# design.net
KiCad netlist of a schematic drawn in Altium Designer
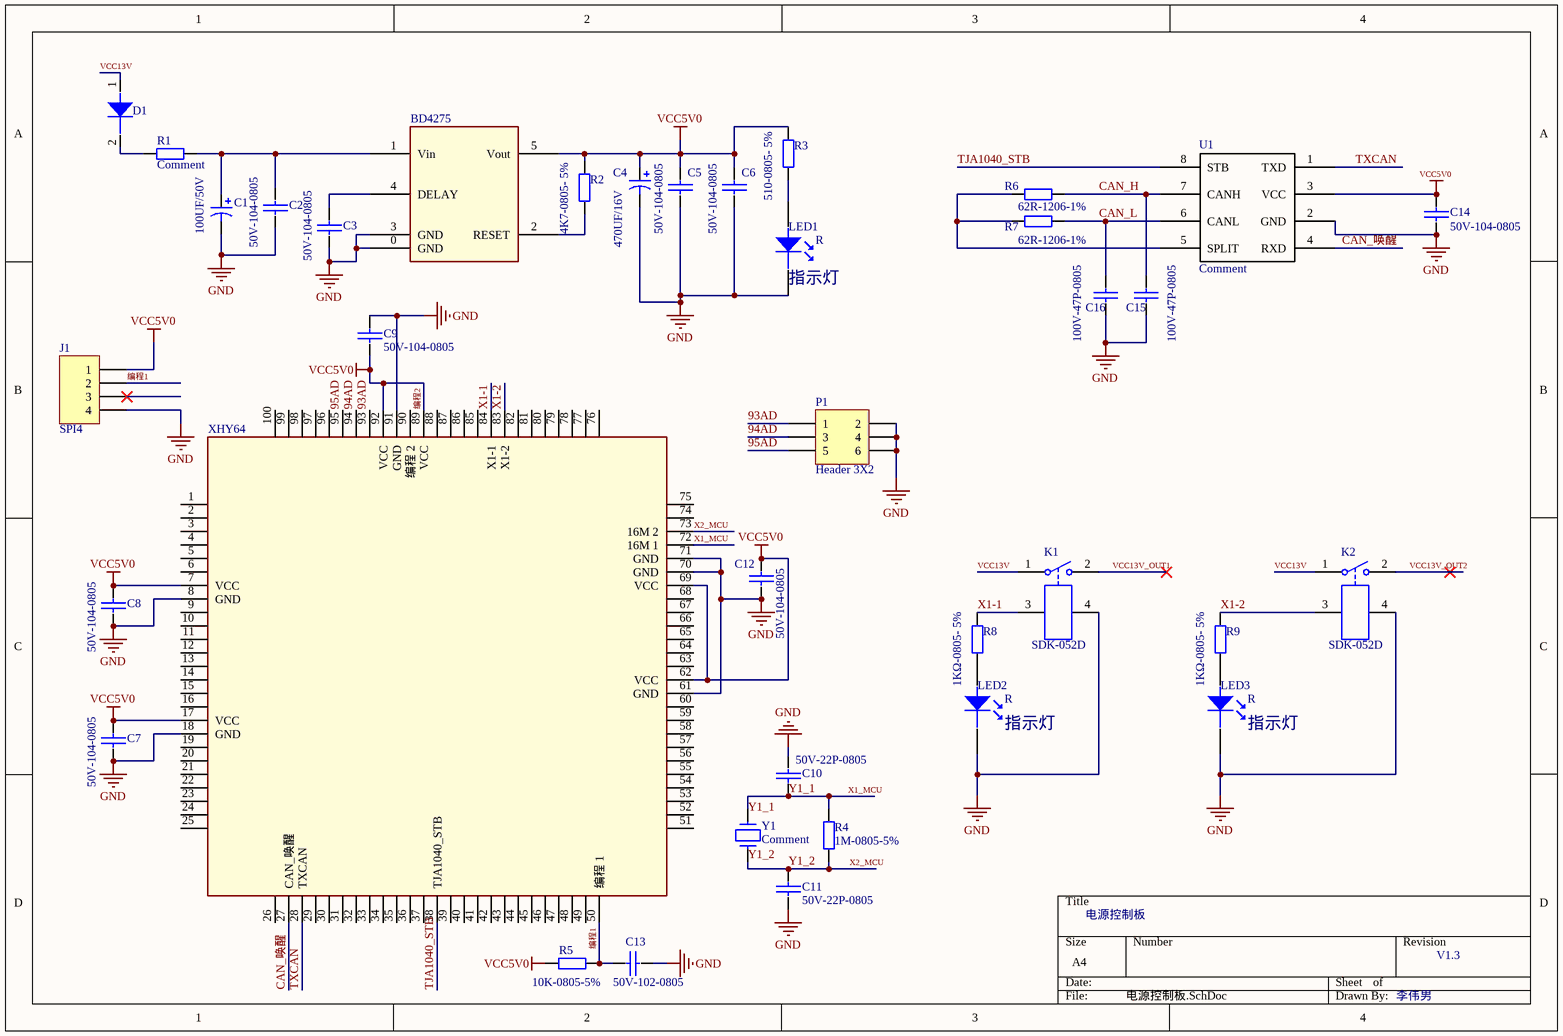
[diagram p0: 电源控制板.SchDoc]

(export (version "E")
  (design (tool "Eeschema 10.0.6"))
  (components
    (comp (ref "BD4275") (value "BD4275") (footprint "TO-263") (libsource (lib "Schlib1") (part "BD4275")))
    (comp (ref "C1")
      (value "100UF/50V")
      (footprint "RB.1/.25")
      (description "100UF      50V")
      (libsource (lib "平台图库_20170418_V1.0") (part "C470UF035S"))
    )
    (comp (ref "C2")
      (value "50V-104-0805")
      (footprint "C0805")
      (description "104     50V        10%   C0805")
      (fields (field (name "Comment") "104"))
      (libsource (lib "平台图库_20170418_V1.0") (part "C104_0805"))
    )
    (comp (ref "C3")
      (value "50V-104-0805")
      (footprint "C0805")
      (description "104     50V        10%   C0805")
      (fields (field (name "Comment") "104"))
      (libsource (lib "平台图库_20170418_V1.0") (part "C104_0805"))
    )
    (comp (ref "C4")
      (value "470UF/16V")
      (footprint "RB.1/.25")
      (description "100UF      50V      CD10X10D5")
      (libsource (lib "平台图库_20170418_V1.0") (part "C470UF016S"))
    )
    (comp (ref "C5")
      (value "50V-104-0805")
      (footprint "C0805")
      (description "104     50V        10%   C0805")
      (fields (field (name "Comment") "104"))
      (libsource (lib "平台图库_20170418_V1.0") (part "C104_0805"))
    )
    (comp (ref "C6")
      (value "50V-104-0805")
      (footprint "C0805")
      (description "104     50V        10%   C0805")
      (fields (field (name "Comment") "104"))
      (libsource (lib "平台图库_20170418_V1.0") (part "C104_0805"))
    )
    (comp (ref "C7")
      (value "50V-104-0805")
      (footprint "C0805")
      (description "104     50V        10%   C0805")
      (fields (field (name "Comment") "104"))
      (libsource (lib "平台图库_20170418_V1.0") (part "C104_0805"))
    )
    (comp (ref "C8")
      (value "50V-104-0805")
      (footprint "C0805")
      (description "104     50V        10%   C0805")
      (fields (field (name "Comment") "104"))
      (libsource (lib "平台图库_20170418_V1.0") (part "C104_0805"))
    )
    (comp (ref "C9")
      (value "50V-104-0805")
      (footprint "C0805")
      (description "104     50V        10%   C0805")
      (fields (field (name "Comment") "104"))
      (libsource (lib "平台图库_20170418_V1.0") (part "C104_0805"))
    )
    (comp (ref "C10")
      (value "50V-22P-0805")
      (footprint "C0805")
      (description "22P     50V        10%   C0805")
      (fields (field (name "Comment") "22P"))
      (libsource (lib "平台图库_20170418_V1.0") (part "C22P_0805"))
    )
    (comp (ref "C11")
      (value "50V-22P-0805")
      (footprint "C0805")
      (description "22P     50V        10%   C0805")
      (fields (field (name "Comment") "22P"))
      (libsource (lib "平台图库_20170418_V1.0") (part "C22P_0805"))
    )
    (comp (ref "C12")
      (value "50V-104-0805")
      (footprint "C0805")
      (description "104     50V        10%   C0805")
      (fields (field (name "Comment") "104"))
      (libsource (lib "平台图库_20170418_V1.0") (part "C104_0805"))
    )
    (comp (ref "C13")
      (value "50V-102-0805")
      (footprint "C0805")
      (description "104     50V        10%   C0805")
      (fields (field (name "Comment") "104"))
      (libsource (lib "平台图库_20170418_V1.0") (part "C102_0805"))
    )
    (comp (ref "C14")
      (value "50V-104-0805")
      (footprint "C0805")
      (description "104     50V        10%   C0805")
      (fields (field (name "Comment") "104"))
      (libsource (lib "平台图库_20170418_V1.0") (part "C104_0805"))
    )
    (comp (ref "C15")
      (value "100V-47P-0805")
      (footprint "C0805")
      (description "47P    100V        10%   C0805")
      (fields (field (name "Comment") "47P-100V"))
      (libsource (lib "平台图库_20170418_V1.0") (part "C47P_100V_0805"))
    )
    (comp (ref "C16")
      (value "100V-47P-0805")
      (footprint "C0805")
      (description "47P    100V        10%   C0805")
      (fields (field (name "Comment") "47P-100V"))
      (libsource (lib "平台图库_20170418_V1.0") (part "C47P_100V_0805"))
    )
    (comp (ref "D1") (value "M7") (footprint "M7-A") (libsource (lib "平台图库_20170418_V1.0") (part "TVS")))
    (comp (ref "J1")
      (value "SPI4")
      (footprint "HDR1X4")
      (description "单排针，Header, 4-Pin")
      (fields (field (name "PUBLISHER") "Altium Limited"))
      (libsource (lib "TYW_Discrete") (part "Header 4"))
    )
    (comp (ref "K1")
      (value "SDK-052D")
      (footprint "SDK-052D")
      (fields (field (name "PUBLISHER") "Altium Limited"))
      (libsource (lib "Miscellaneous Devices") (part "Relay-SPST"))
    )
    (comp (ref "K2")
      (value "SDK-052D")
      (footprint "SDK-052D")
      (fields (field (name "PUBLISHER") "Altium Limited"))
      (libsource (lib "Miscellaneous Devices") (part "Relay-SPST"))
    )
    (comp (ref "LED1")
      (value "R")
      (footprint "1206-2")
      (description "LED_R")
      (libsource (lib "平台图库_20170418_V1.0") (part "LED_R"))
    )
    (comp (ref "LED2")
      (value "R")
      (footprint "1206-2")
      (description "LED_R")
      (libsource (lib "平台图库_20170418_V1.0") (part "LED_R"))
    )
    (comp (ref "LED3")
      (value "R")
      (footprint "1206-2")
      (description "LED_R")
      (libsource (lib "平台图库_20170418_V1.0") (part "LED_R"))
    )
    (comp (ref "P1")
      (value "Header 3X2")
      (footprint "HDR2X3")
      (description "Header, 3-Pin, Dual row")
      (fields (field (name "PUBLISHER") "Altium Limited"))
      (libsource (lib "Miscellaneous Connectors") (part "Header 3X2"))
    )
    (comp (ref "R1")
      (value "Comment")
      (footprint "2WR")
      (description "8R2                                2W")
      (libsource (lib "平台图库_20170418_V1.0") (part "R8R22W"))
    )
    (comp (ref "R2")
      (value "4K7-0805- 5%")
      (footprint "0805")
      (description "4K7     1/8W    5%   R0805")
      (fields (field (name "Comment") "4K7"))
      (libsource (lib "平台图库_20170418_V1.0") (part "R4K7_0805_5%"))
    )
    (comp (ref "R3")
      (value "510-0805- 5%")
      (footprint "0805_2")
      (description "510Ω    5%   R0805")
      (fields (field (name "Comment") "510Ω"))
      (libsource (lib "Miscellaneous Connectors") (part "R4K7_0805_5%"))
    )
    (comp (ref "R4")
      (value "1M-0805-5%")
      (footprint "0805")
      (description "1M    1/8W    5%   R0805")
      (fields (field (name "Comment") "1M"))
      (libsource (lib "平台图库_20170418_V1.0") (part "R1M_0805_5%"))
    )
    (comp (ref "R5")
      (value "10K-0805-5%")
      (footprint "0805")
      (description "10K     1/8W    5%   R0805")
      (fields (field (name "Comment") "10K"))
      (libsource (lib "平台图库_20170418_V1.0") (part "R10K_0805_5%"))
    )
    (comp (ref "R6")
      (value "62R-1206-1%")
      (footprint "1206")
      (description "62R    1/4W     1%   R1206")
      (fields (field (name "Comment") "62R-J"))
      (libsource (lib "平台图库_20170418_V1.0") (part "R62R_1206_1%"))
    )
    (comp (ref "R7")
      (value "62R-1206-1%")
      (footprint "1206")
      (description "62R    1/4W     1%   R1206")
      (fields (field (name "Comment") "62R-J"))
      (libsource (lib "平台图库_20170418_V1.0") (part "R62R_1206_1%"))
    )
    (comp (ref "R8")
      (value "1KΩ-0805- 5%")
      (footprint "0805_2")
      (description "1KΩ    5%   R0805")
      (fields (field (name "Comment") "1KΩ"))
      (libsource (lib "Miscellaneous Connectors") (part "R4K7_0805_5%"))
    )
    (comp (ref "R9")
      (value "1KΩ-0805- 5%")
      (footprint "0805_2")
      (description "1KΩ    5%   R0805")
      (fields (field (name "Comment") "1KΩ"))
      (libsource (lib "Miscellaneous Connectors") (part "R4K7_0805_5%"))
    )
    (comp (ref "U1")
      (value "Comment")
      (footprint "SO-8")
      (description "CAN驱动芯片")
      (libsource (lib "平台图库_20170418_V1.0") (part "TJA1042"))
    )
    (comp (ref "XHY64") (value "XHY64") (footprint "QUAD100") (libsource (lib "Schlib1") (part "XHY64")))
    (comp (ref "Y1")
      (value "Comment")
      (footprint "16M")
      (description "晶体，4M")
      (libsource (lib "TYW_Discrete") (part "XTAL"))
    )
  )
  (nets
    (net (code "1") (name "/93AD") (class "Default")
      (node (ref "P1") (pin "1") (pinfunction "1_1") (pintype "passive"))
      (node (ref "XHY64") (pin "93") (pintype "passive"))
    )
    (net (code "2") (name "/94AD") (class "Default")
      (node (ref "P1") (pin "3") (pinfunction "3_3") (pintype "passive"))
      (node (ref "XHY64") (pin "94") (pintype "passive"))
    )
    (net (code "3") (name "/95AD") (class "Default")
      (node (ref "P1") (pin "5") (pinfunction "5_5") (pintype "passive"))
      (node (ref "XHY64") (pin "95") (pintype "passive"))
    )
    (net (code "4") (name "/CAN_H") (class "Default")
      (node (ref "C15") (pin "2") (pinfunction "2_2") (pintype "passive"))
      (node (ref "R6") (pin "2") (pinfunction "2_2") (pintype "passive"))
      (node (ref "U1") (pin "7") (pinfunction "CANH_7") (pintype "passive"))
    )
    (net (code "5") (name "/CAN_L") (class "Default")
      (node (ref "C16") (pin "2") (pinfunction "2_2") (pintype "passive"))
      (node (ref "R7") (pin "2") (pinfunction "2_2") (pintype "passive"))
      (node (ref "U1") (pin "6") (pinfunction "CANL_6") (pintype "passive"))
    )
    (net (code "6") (name "/CAN_唤醒") (class "Default")
      (node (ref "U1") (pin "4") (pinfunction "RXD_4") (pintype "passive"))
      (node (ref "XHY64") (pin "27") (pinfunction "CAN_唤醒_27") (pintype "passive"))
    )
    (net (code "7") (name "/TJA1040_STB") (class "Default")
      (node (ref "U1") (pin "8") (pinfunction "STB_8") (pintype "passive"))
      (node (ref "XHY64") (pin "38") (pinfunction "TJA1040_STB_38") (pintype "passive"))
    )
    (net (code "8") (name "/TXCAN") (class "Default")
      (node (ref "U1") (pin "1") (pinfunction "TXD_1") (pintype "passive"))
      (node (ref "XHY64") (pin "28") (pinfunction "TXCAN_28") (pintype "passive"))
    )
    (net (code "9") (name "/VCC13V") (class "Default")
      (node (ref "D1") (pin "1") (pinfunction "1_1") (pintype "passive"))
      (node (ref "K1") (pin "1") (pinfunction "1_1") (pintype "passive"))
      (node (ref "K2") (pin "1") (pinfunction "1_1") (pintype "passive"))
    )
    (net (code "10") (name "/VCC13V_OUT1") (class "Default")
      (node (ref "K1") (pin "2") (pinfunction "2_2") (pintype "passive+no_connect"))
    )
    (net (code "11") (name "/VCC13V_OUT2") (class "Default")
      (node (ref "K2") (pin "2") (pinfunction "2_2") (pintype "passive"))
    )
    (net (code "12") (name "/X1-1") (class "Default")
      (node (ref "K1") (pin "3") (pinfunction "3_3") (pintype "passive"))
      (node (ref "R8") (pin "2") (pinfunction "2_2") (pintype "passive"))
      (node (ref "XHY64") (pin "84") (pinfunction "X1-1_84") (pintype "passive"))
    )
    (net (code "13") (name "/X1-2") (class "Default")
      (node (ref "K2") (pin "3") (pinfunction "3_3") (pintype "passive"))
      (node (ref "R9") (pin "2") (pinfunction "2_2") (pintype "passive"))
      (node (ref "XHY64") (pin "83") (pinfunction "X1-2_83") (pintype "passive"))
    )
    (net (code "14") (name "/X1_MCU") (class "Default")
      (node (ref "C10") (pin "2") (pinfunction "2_2") (pintype "passive"))
      (node (ref "R4") (pin "2") (pinfunction "2_2") (pintype "passive"))
      (node (ref "XHY64") (pin "72") (pinfunction "16M_1_72") (pintype "passive"))
      (node (ref "Y1") (pin "2") (pinfunction "2_2") (pintype "passive"))
    )
    (net (code "15") (name "/X2_MCU") (class "Default")
      (node (ref "C11") (pin "1") (pinfunction "1_1") (pintype "passive"))
      (node (ref "R4") (pin "1") (pinfunction "1_1") (pintype "passive"))
      (node (ref "XHY64") (pin "73") (pinfunction "16M_2_73") (pintype "passive"))
      (node (ref "Y1") (pin "1") (pinfunction "1_1") (pintype "passive"))
    )
    (net (code "16") (name "/编程1") (class "Default")
      (node (ref "C13") (pin "2") (pinfunction "2_2") (pintype "passive"))
      (node (ref "J1") (pin "2") (pinfunction "2_2") (pintype "passive"))
      (node (ref "R5") (pin "1") (pinfunction "1_1") (pintype "passive"))
      (node (ref "XHY64") (pin "50") (pinfunction "编程_1_50") (pintype "passive"))
    )
    (net (code "17") (name "GND") (class "Default")
      (node (ref "BD4275") (pin "0") (pinfunction "GND_0") (pintype "passive"))
      (node (ref "BD4275") (pin "3") (pinfunction "GND_3") (pintype "passive"))
      (node (ref "C1") (pin "2") (pinfunction "2_2") (pintype "passive"))
      (node (ref "C10") (pin "1") (pinfunction "1_1") (pintype "passive"))
      (node (ref "C11") (pin "2") (pinfunction "2_2") (pintype "passive"))
      (node (ref "C12") (pin "2") (pinfunction "2_2") (pintype "passive"))
      (node (ref "C13") (pin "1") (pinfunction "1_1") (pintype "passive"))
      (node (ref "C14") (pin "1") (pinfunction "1_1") (pintype "passive"))
      (node (ref "C15") (pin "1") (pinfunction "1_1") (pintype "passive"))
      (node (ref "C16") (pin "1") (pinfunction "1_1") (pintype "passive"))
      (node (ref "C2") (pin "1") (pinfunction "1_1") (pintype "passive"))
      (node (ref "C3") (pin "1") (pinfunction "1_1") (pintype "passive"))
      (node (ref "C4") (pin "2") (pinfunction "2_2") (pintype "passive"))
      (node (ref "C5") (pin "1") (pinfunction "1_1") (pintype "passive"))
      (node (ref "C6") (pin "1") (pinfunction "1_1") (pintype "passive"))
      (node (ref "C7") (pin "2") (pinfunction "2_2") (pintype "passive"))
      (node (ref "C8") (pin "2") (pinfunction "2_2") (pintype "passive"))
      (node (ref "C9") (pin "1") (pinfunction "1_1") (pintype "passive"))
      (node (ref "J1") (pin "4") (pinfunction "4_4") (pintype "passive"))
      (node (ref "K1") (pin "4") (pinfunction "4_4") (pintype "passive"))
      (node (ref "K2") (pin "4") (pinfunction "4_4") (pintype "passive"))
      (node (ref "LED1") (pin "2") (pinfunction "2_2") (pintype "passive"))
      (node (ref "LED2") (pin "2") (pinfunction "2_2") (pintype "passive"))
      (node (ref "LED3") (pin "2") (pinfunction "2_2") (pintype "passive"))
      (node (ref "P1") (pin "2") (pinfunction "2_2") (pintype "passive"))
      (node (ref "P1") (pin "4") (pinfunction "4_4") (pintype "passive"))
      (node (ref "P1") (pin "6") (pinfunction "6_6") (pintype "passive"))
      (node (ref "U1") (pin "2") (pinfunction "GND_2") (pintype "passive"))
      (node (ref "XHY64") (pin "18") (pinfunction "GND_18") (pintype "passive"))
      (node (ref "XHY64") (pin "61") (pinfunction "GND_61") (pintype "passive"))
      (node (ref "XHY64") (pin "70") (pinfunction "GND_70") (pintype "passive"))
      (node (ref "XHY64") (pin "71") (pinfunction "GND_71") (pintype "passive"))
      (node (ref "XHY64") (pin "8") (pinfunction "GND_8") (pintype "passive"))
      (node (ref "XHY64") (pin "91") (pinfunction "GND_91") (pintype "passive"))
    )
    (net (code "18") (name "Net-(BD4275-DELAY)") (class "Default")
      (node (ref "BD4275") (pin "4") (pinfunction "DELAY_4") (pintype "passive"))
      (node (ref "C3") (pin "2") (pinfunction "2_2") (pintype "passive"))
    )
    (net (code "19") (name "Net-(BD4275-RESET)") (class "Default")
      (node (ref "BD4275") (pin "2") (pinfunction "RESET_2") (pintype "passive"))
      (node (ref "R2") (pin "1") (pinfunction "1_1") (pintype "passive"))
    )
    (net (code "20") (name "Net-(BD4275-Vin)") (class "Default")
      (node (ref "BD4275") (pin "1") (pinfunction "Vin_1") (pintype "passive"))
      (node (ref "C1") (pin "1") (pinfunction "1_1") (pintype "passive"))
      (node (ref "C2") (pin "2") (pinfunction "2_2") (pintype "passive"))
      (node (ref "R1") (pin "1") (pinfunction "1_1") (pintype "passive"))
    )
    (net (code "21") (name "Net-(D1-Pad2)") (class "Default")
      (node (ref "D1") (pin "2") (pinfunction "2_2") (pintype "passive"))
      (node (ref "R1") (pin "2") (pinfunction "2_2") (pintype "passive"))
    )
    (net (code "22") (name "Net-(LED1-Pad1)") (class "Default")
      (node (ref "LED1") (pin "1") (pinfunction "1_1") (pintype "passive"))
      (node (ref "R3") (pin "1") (pinfunction "1_1") (pintype "passive"))
    )
    (net (code "23") (name "Net-(U1-SPLIT)") (class "Default")
      (node (ref "R6") (pin "1") (pinfunction "1_1") (pintype "passive"))
      (node (ref "R7") (pin "1") (pinfunction "1_1") (pintype "passive"))
      (node (ref "U1") (pin "5") (pinfunction "SPLIT_5") (pintype "passive"))
    )
    (net (code "24") (name "VCC5V0") (class "Default")
      (node (ref "BD4275") (pin "5") (pinfunction "Vout_5") (pintype "passive"))
      (node (ref "C12") (pin "1") (pinfunction "1_1") (pintype "passive"))
      (node (ref "C14") (pin "2") (pinfunction "2_2") (pintype "passive"))
      (node (ref "C4") (pin "1") (pinfunction "1_1") (pintype "passive"))
      (node (ref "C5") (pin "2") (pinfunction "2_2") (pintype "passive"))
      (node (ref "C6") (pin "2") (pinfunction "2_2") (pintype "passive"))
      (node (ref "C7") (pin "1") (pinfunction "1_1") (pintype "passive"))
      (node (ref "C8") (pin "1") (pinfunction "1_1") (pintype "passive"))
      (node (ref "C9") (pin "2") (pinfunction "2_2") (pintype "passive"))
      (node (ref "J1") (pin "1") (pinfunction "1_1") (pintype "passive"))
      (node (ref "R2") (pin "2") (pinfunction "2_2") (pintype "passive"))
      (node (ref "R3") (pin "2") (pinfunction "2_2") (pintype "passive"))
      (node (ref "R5") (pin "2") (pinfunction "2_2") (pintype "passive"))
      (node (ref "U1") (pin "3") (pinfunction "VCC_3") (pintype "passive"))
      (node (ref "XHY64") (pin "17") (pinfunction "VCC_17") (pintype "passive"))
      (node (ref "XHY64") (pin "62") (pinfunction "VCC_62") (pintype "passive"))
      (node (ref "XHY64") (pin "69") (pinfunction "VCC_69") (pintype "passive"))
      (node (ref "XHY64") (pin "7") (pinfunction "VCC_7") (pintype "passive"))
      (node (ref "XHY64") (pin "89") (pinfunction "VCC_89") (pintype "passive"))
      (node (ref "XHY64") (pin "92") (pinfunction "VCC_92") (pintype "passive"))
    )
    (net (code "25") (name "unconnected-(J1-Pad3)") (class "Default")
      (node (ref "J1") (pin "3") (pinfunction "3_3") (pintype "passive+no_connect"))
    )
    (net (code "26") (name "unconnected-(LED2-Pad1)") (class "Default")
      (node (ref "LED2") (pin "1") (pinfunction "1_1") (pintype "passive"))
    )
    (net (code "27") (name "unconnected-(LED3-Pad1)") (class "Default")
      (node (ref "LED3") (pin "1") (pinfunction "1_1") (pintype "passive"))
    )
    (net (code "28") (name "unconnected-(R8-Pad1)") (class "Default")
      (node (ref "R8") (pin "1") (pinfunction "1_1") (pintype "passive"))
    )
    (net (code "29") (name "unconnected-(R9-Pad1)") (class "Default")
      (node (ref "R9") (pin "1") (pinfunction "1_1") (pintype "passive"))
    )
    (net (code "30") (name "unconnected-(XHY64-Pad1)") (class "Default")
      (node (ref "XHY64") (pin "1") (pintype "passive"))
    )
    (net (code "31") (name "unconnected-(XHY64-Pad2)") (class "Default")
      (node (ref "XHY64") (pin "2") (pintype "passive"))
    )
    (net (code "32") (name "unconnected-(XHY64-Pad3)") (class "Default")
      (node (ref "XHY64") (pin "3") (pintype "passive"))
    )
    (net (code "33") (name "unconnected-(XHY64-Pad4)") (class "Default")
      (node (ref "XHY64") (pin "4") (pintype "passive"))
    )
    (net (code "34") (name "unconnected-(XHY64-Pad5)") (class "Default")
      (node (ref "XHY64") (pin "5") (pintype "passive"))
    )
    (net (code "35") (name "unconnected-(XHY64-Pad6)") (class "Default")
      (node (ref "XHY64") (pin "6") (pintype "passive"))
    )
    (net (code "36") (name "unconnected-(XHY64-Pad9)") (class "Default")
      (node (ref "XHY64") (pin "9") (pintype "passive"))
    )
    (net (code "37") (name "unconnected-(XHY64-Pad10)") (class "Default")
      (node (ref "XHY64") (pin "10") (pintype "passive"))
    )
    (net (code "38") (name "unconnected-(XHY64-Pad11)") (class "Default")
      (node (ref "XHY64") (pin "11") (pintype "passive"))
    )
    (net (code "39") (name "unconnected-(XHY64-Pad12)") (class "Default")
      (node (ref "XHY64") (pin "12") (pintype "passive"))
    )
    (net (code "40") (name "unconnected-(XHY64-Pad13)") (class "Default")
      (node (ref "XHY64") (pin "13") (pintype "passive"))
    )
    (net (code "41") (name "unconnected-(XHY64-Pad14)") (class "Default")
      (node (ref "XHY64") (pin "14") (pintype "passive"))
    )
    (net (code "42") (name "unconnected-(XHY64-Pad15)") (class "Default")
      (node (ref "XHY64") (pin "15") (pintype "passive"))
    )
    (net (code "43") (name "unconnected-(XHY64-Pad16)") (class "Default")
      (node (ref "XHY64") (pin "16") (pintype "passive"))
    )
    (net (code "44") (name "unconnected-(XHY64-Pad19)") (class "Default")
      (node (ref "XHY64") (pin "19") (pintype "passive"))
    )
    (net (code "45") (name "unconnected-(XHY64-Pad20)") (class "Default")
      (node (ref "XHY64") (pin "20") (pintype "passive"))
    )
    (net (code "46") (name "unconnected-(XHY64-Pad21)") (class "Default")
      (node (ref "XHY64") (pin "21") (pintype "passive"))
    )
    (net (code "47") (name "unconnected-(XHY64-Pad22)") (class "Default")
      (node (ref "XHY64") (pin "22") (pintype "passive"))
    )
    (net (code "48") (name "unconnected-(XHY64-Pad23)") (class "Default")
      (node (ref "XHY64") (pin "23") (pintype "passive"))
    )
    (net (code "49") (name "unconnected-(XHY64-Pad24)") (class "Default")
      (node (ref "XHY64") (pin "24") (pintype "passive"))
    )
    (net (code "50") (name "unconnected-(XHY64-Pad25)") (class "Default")
      (node (ref "XHY64") (pin "25") (pintype "passive"))
    )
    (net (code "51") (name "unconnected-(XHY64-Pad26)") (class "Default")
      (node (ref "XHY64") (pin "26") (pintype "passive"))
    )
    (net (code "52") (name "unconnected-(XHY64-Pad29)") (class "Default")
      (node (ref "XHY64") (pin "29") (pintype "passive"))
    )
    (net (code "53") (name "unconnected-(XHY64-Pad30)") (class "Default")
      (node (ref "XHY64") (pin "30") (pintype "passive"))
    )
    (net (code "54") (name "unconnected-(XHY64-Pad31)") (class "Default")
      (node (ref "XHY64") (pin "31") (pintype "passive"))
    )
    (net (code "55") (name "unconnected-(XHY64-Pad32)") (class "Default")
      (node (ref "XHY64") (pin "32") (pintype "passive"))
    )
    (net (code "56") (name "unconnected-(XHY64-Pad33)") (class "Default")
      (node (ref "XHY64") (pin "33") (pintype "passive"))
    )
    (net (code "57") (name "unconnected-(XHY64-Pad34)") (class "Default")
      (node (ref "XHY64") (pin "34") (pintype "passive"))
    )
    (net (code "58") (name "unconnected-(XHY64-Pad35)") (class "Default")
      (node (ref "XHY64") (pin "35") (pintype "passive"))
    )
    (net (code "59") (name "unconnected-(XHY64-Pad36)") (class "Default")
      (node (ref "XHY64") (pin "36") (pintype "passive"))
    )
    (net (code "60") (name "unconnected-(XHY64-Pad37)") (class "Default")
      (node (ref "XHY64") (pin "37") (pintype "passive"))
    )
    (net (code "61") (name "unconnected-(XHY64-Pad39)") (class "Default")
      (node (ref "XHY64") (pin "39") (pintype "passive"))
    )
    (net (code "62") (name "unconnected-(XHY64-Pad40)") (class "Default")
      (node (ref "XHY64") (pin "40") (pintype "passive"))
    )
    (net (code "63") (name "unconnected-(XHY64-Pad41)") (class "Default")
      (node (ref "XHY64") (pin "41") (pintype "passive"))
    )
    (net (code "64") (name "unconnected-(XHY64-Pad42)") (class "Default")
      (node (ref "XHY64") (pin "42") (pintype "passive"))
    )
    (net (code "65") (name "unconnected-(XHY64-Pad43)") (class "Default")
      (node (ref "XHY64") (pin "43") (pintype "passive"))
    )
    (net (code "66") (name "unconnected-(XHY64-Pad44)") (class "Default")
      (node (ref "XHY64") (pin "44") (pintype "passive"))
    )
    (net (code "67") (name "unconnected-(XHY64-Pad45)") (class "Default")
      (node (ref "XHY64") (pin "45") (pintype "passive"))
    )
    (net (code "68") (name "unconnected-(XHY64-Pad46)") (class "Default")
      (node (ref "XHY64") (pin "46") (pintype "passive"))
    )
    (net (code "69") (name "unconnected-(XHY64-Pad47)") (class "Default")
      (node (ref "XHY64") (pin "47") (pintype "passive"))
    )
    (net (code "70") (name "unconnected-(XHY64-Pad48)") (class "Default")
      (node (ref "XHY64") (pin "48") (pintype "passive"))
    )
    (net (code "71") (name "unconnected-(XHY64-Pad49)") (class "Default")
      (node (ref "XHY64") (pin "49") (pintype "passive"))
    )
    (net (code "72") (name "unconnected-(XHY64-Pad51)") (class "Default")
      (node (ref "XHY64") (pin "51") (pintype "passive"))
    )
    (net (code "73") (name "unconnected-(XHY64-Pad52)") (class "Default")
      (node (ref "XHY64") (pin "52") (pintype "passive"))
    )
    (net (code "74") (name "unconnected-(XHY64-Pad53)") (class "Default")
      (node (ref "XHY64") (pin "53") (pintype "passive"))
    )
    (net (code "75") (name "unconnected-(XHY64-Pad54)") (class "Default")
      (node (ref "XHY64") (pin "54") (pintype "passive"))
    )
    (net (code "76") (name "unconnected-(XHY64-Pad55)") (class "Default")
      (node (ref "XHY64") (pin "55") (pintype "passive"))
    )
    (net (code "77") (name "unconnected-(XHY64-Pad56)") (class "Default")
      (node (ref "XHY64") (pin "56") (pintype "passive"))
    )
    (net (code "78") (name "unconnected-(XHY64-Pad57)") (class "Default")
      (node (ref "XHY64") (pin "57") (pintype "passive"))
    )
    (net (code "79") (name "unconnected-(XHY64-Pad58)") (class "Default")
      (node (ref "XHY64") (pin "58") (pintype "passive"))
    )
    (net (code "80") (name "unconnected-(XHY64-Pad59)") (class "Default")
      (node (ref "XHY64") (pin "59") (pintype "passive"))
    )
    (net (code "81") (name "unconnected-(XHY64-Pad60)") (class "Default")
      (node (ref "XHY64") (pin "60") (pintype "passive"))
    )
    (net (code "82") (name "unconnected-(XHY64-Pad63)") (class "Default")
      (node (ref "XHY64") (pin "63") (pintype "passive"))
    )
    (net (code "83") (name "unconnected-(XHY64-Pad64)") (class "Default")
      (node (ref "XHY64") (pin "64") (pintype "passive"))
    )
    (net (code "84") (name "unconnected-(XHY64-Pad65)") (class "Default")
      (node (ref "XHY64") (pin "65") (pintype "passive"))
    )
    (net (code "85") (name "unconnected-(XHY64-Pad66)") (class "Default")
      (node (ref "XHY64") (pin "66") (pintype "passive"))
    )
    (net (code "86") (name "unconnected-(XHY64-Pad67)") (class "Default")
      (node (ref "XHY64") (pin "67") (pintype "passive"))
    )
    (net (code "87") (name "unconnected-(XHY64-Pad68)") (class "Default")
      (node (ref "XHY64") (pin "68") (pintype "passive"))
    )
    (net (code "88") (name "unconnected-(XHY64-Pad74)") (class "Default")
      (node (ref "XHY64") (pin "74") (pintype "passive"))
    )
    (net (code "89") (name "unconnected-(XHY64-Pad75)") (class "Default")
      (node (ref "XHY64") (pin "75") (pintype "passive"))
    )
    (net (code "90") (name "unconnected-(XHY64-Pad76)") (class "Default")
      (node (ref "XHY64") (pin "76") (pintype "passive"))
    )
    (net (code "91") (name "unconnected-(XHY64-Pad77)") (class "Default")
      (node (ref "XHY64") (pin "77") (pintype "passive"))
    )
    (net (code "92") (name "unconnected-(XHY64-Pad78)") (class "Default")
      (node (ref "XHY64") (pin "78") (pintype "passive"))
    )
    (net (code "93") (name "unconnected-(XHY64-Pad79)") (class "Default")
      (node (ref "XHY64") (pin "79") (pintype "passive"))
    )
    (net (code "94") (name "unconnected-(XHY64-Pad80)") (class "Default")
      (node (ref "XHY64") (pin "80") (pintype "passive"))
    )
    (net (code "95") (name "unconnected-(XHY64-Pad81)") (class "Default")
      (node (ref "XHY64") (pin "81") (pintype "passive"))
    )
    (net (code "96") (name "unconnected-(XHY64-Pad82)") (class "Default")
      (node (ref "XHY64") (pin "82") (pintype "passive"))
    )
    (net (code "97") (name "unconnected-(XHY64-Pad85)") (class "Default")
      (node (ref "XHY64") (pin "85") (pintype "passive"))
    )
    (net (code "98") (name "unconnected-(XHY64-Pad86)") (class "Default")
      (node (ref "XHY64") (pin "86") (pintype "passive"))
    )
    (net (code "99") (name "unconnected-(XHY64-Pad87)") (class "Default")
      (node (ref "XHY64") (pin "87") (pintype "passive"))
    )
    (net (code "100") (name "unconnected-(XHY64-Pad88)") (class "Default")
      (node (ref "XHY64") (pin "88") (pintype "passive"))
    )
    (net (code "101") (name "unconnected-(XHY64-Pad96)") (class "Default")
      (node (ref "XHY64") (pin "96") (pintype "passive"))
    )
    (net (code "102") (name "unconnected-(XHY64-Pad97)") (class "Default")
      (node (ref "XHY64") (pin "97") (pintype "passive"))
    )
    (net (code "103") (name "unconnected-(XHY64-Pad98)") (class "Default")
      (node (ref "XHY64") (pin "98") (pintype "passive"))
    )
    (net (code "104") (name "unconnected-(XHY64-Pad99)") (class "Default")
      (node (ref "XHY64") (pin "99") (pintype "passive"))
    )
    (net (code "105") (name "unconnected-(XHY64-Pad100)") (class "Default")
      (node (ref "XHY64") (pin "100") (pintype "passive"))
    )
    (net (code "106") (name "unconnected-(XHY64-编程_2-Pad90)") (class "Default")
      (node (ref "XHY64") (pin "90") (pinfunction "编程_2_90") (pintype "passive"))
    )
  )
)
